# fet_driver.net
KiCad netlist of a schematic drawn in Altium Designer
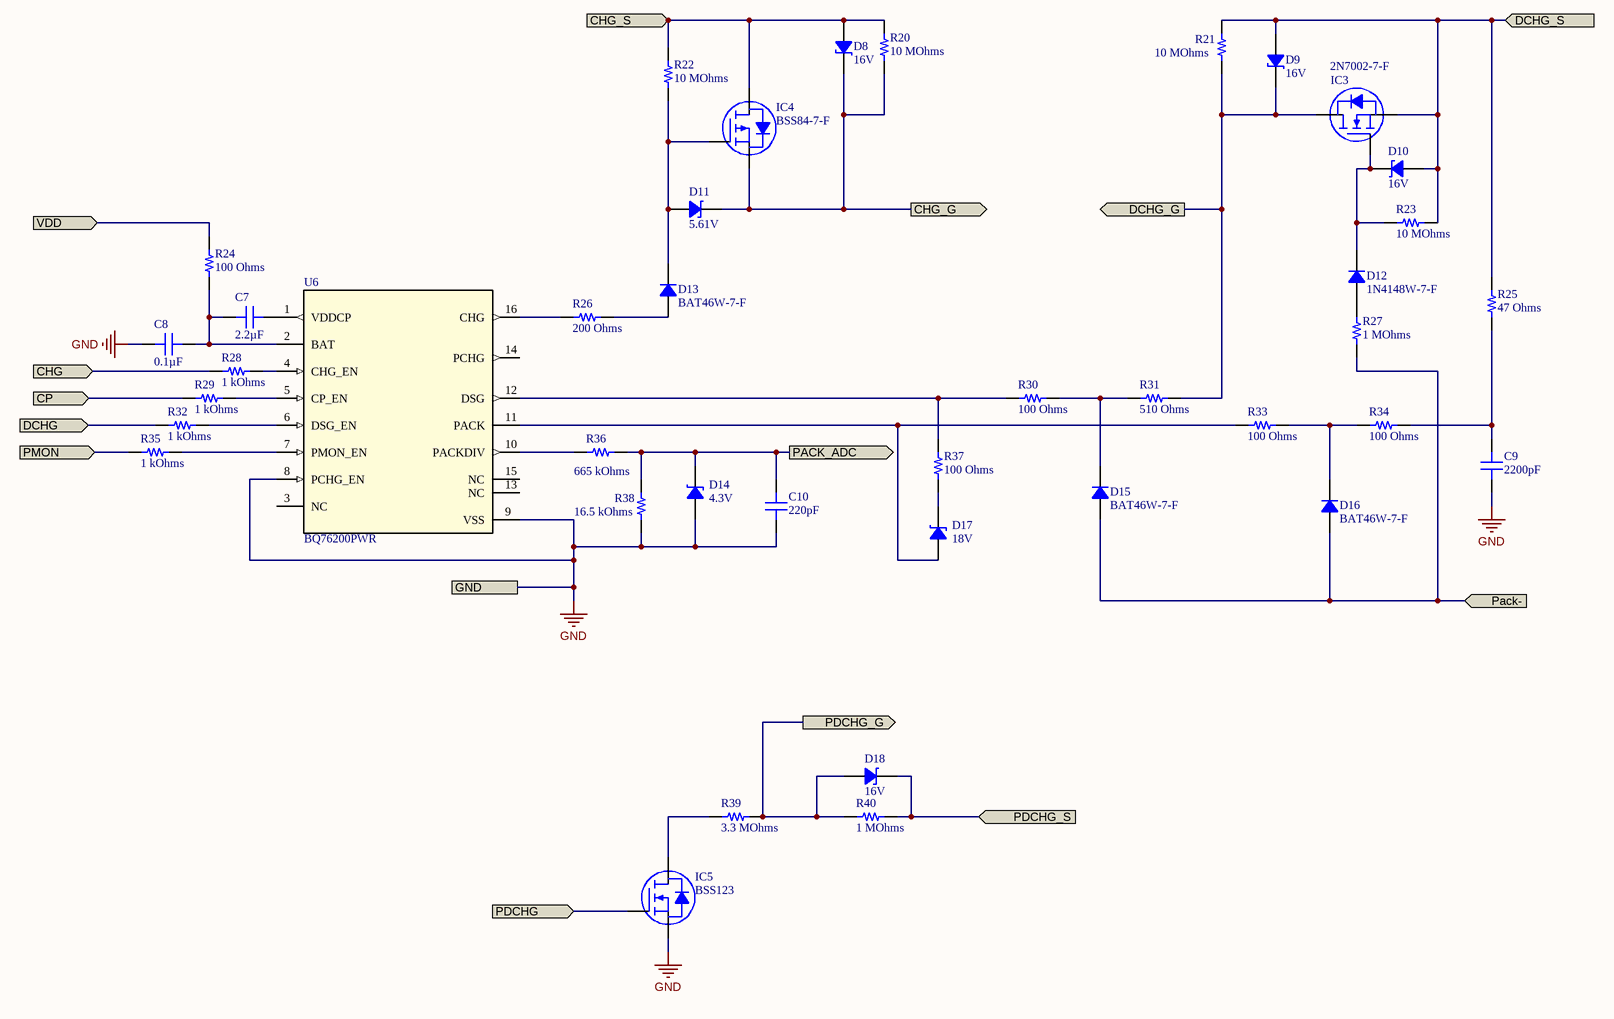
[diagram p0: fet_driver.SchDoc]

(export (version "E")
  (design (tool "Eeschema 10.0.6"))
  (components
    (comp (ref "C7")
      (value "2.2µF")
      (footprint "CAP 1210_3225 - 2.5MM")
      (description "CAP CER 2.2UF 100V X7R 1210")
      (fields
        (field (name "PART NUMBER") "C3225X7R2A225K230AE")
        (field (name "MANUFACTURER") "TDK Corporation")
      )
      (libsource (lib "Celestial Altium Library - altium_library") (part "Capacitor"))
    )
    (comp (ref "C8")
      (value "0.1µF")
      (footprint "CAP 0603_1608")
      (description "CAP CER 0.1UF 100V X7R 0603")
      (fields
        (field (name "PART NUMBER") "GCJ188R72A104KA01D")
        (field (name "MANUFACTURER") "Murata Electronics")
      )
      (libsource (lib "Celestial Altium Library - altium_library") (part "Capacitor"))
    )
    (comp (ref "C9")
      (value "2200pF")
      (footprint "CAP 0603_1608")
      (description "CAP CER 2200PF 100V X7R 0603")
      (fields
        (field (name "PART NUMBER") "CGA3E2X7R2A222K080AE")
        (field (name "MANUFACTURER") "TDK Corporation")
      )
      (libsource (lib "Celestial Altium Library - altium_library") (part "Capacitor"))
    )
    (comp (ref "C10")
      (value "220pF")
      (footprint "CAP 0603_1608")
      (description "CAP CER 220PF 50V X7R 0603")
      (fields (field (name "PART NUMBER") "CC0603KRX7R9BB221") (field (name "MANUFACTURER") "Yageo"))
      (libsource (lib "Celestial Altium Library - altium_library") (part "Capacitor"))
    )
    (comp (ref "D8")
      (value "MMSZ5246B-7-F")
      (footprint "SOD-123")
      (description "DIODE ZENER 16V 500MW SOD123")
      (fields
        (field (name "MANUFACTURER") "Diodes Incorporated")
        (field (name "TOLERANCE") "±5%")
        (field (name "VOLTAGE - ZENER (NOM) (VZ)") "16V")
      )
      (libsource (lib "Celestial Altium Library - altium_library") (part "Diode Zener"))
    )
    (comp (ref "D9")
      (value "MMSZ5246B-7-F")
      (footprint "SOD-123")
      (description "DIODE ZENER 16V 500MW SOD123")
      (fields
        (field (name "MANUFACTURER") "Diodes Incorporated")
        (field (name "TOLERANCE") "±5%")
        (field (name "VOLTAGE - ZENER (NOM) (VZ)") "16V")
      )
      (libsource (lib "Celestial Altium Library - altium_library") (part "Diode Zener"))
    )
    (comp (ref "D10")
      (value "MMSZ5246B-7-F")
      (footprint "SOD-123")
      (description "DIODE ZENER 16V 500MW SOD123")
      (fields
        (field (name "MANUFACTURER") "Diodes Incorporated")
        (field (name "TOLERANCE") "±5%")
        (field (name "VOLTAGE - ZENER (NOM) (VZ)") "16V")
      )
      (libsource (lib "Celestial Altium Library - altium_library") (part "Diode Zener"))
    )
    (comp (ref "D11")
      (value "MM5Z5V6ST1G")
      (footprint "SOD523F")
      (description "DIODE ZENER 5.61V 500MW SOD523")
      (fields
        (field (name "MANUFACTURER") "ON Semiconductor")
        (field (name "TOLERANCE") "±2%")
        (field (name "VOLTAGE - ZENER (NOM) (VZ)") "5.61V")
      )
      (libsource (lib "Celestial Altium Library - altium_library") (part "Diode Zener"))
    )
    (comp (ref "D12")
      (value "1N4148W-7-F")
      (footprint "SOD-123")
      (description "DIODE GEN PURP 100V 300MA SOD123")
      (fields (field (name "MANUFACTURER") "Diodes Incorporated"))
      (libsource (lib "Celestial Altium Library - altium_library") (part "Diode"))
    )
    (comp (ref "D13")
      (value "BAT46W-7-F")
      (footprint "SOD-123")
      (description "DIODE SCHOTTKY 100V 150MA SOD123")
      (fields (field (name "MANUFACTURER") "Diodes Incorporated"))
      (libsource (lib "Celestial Altium Library - altium_library") (part "Diode"))
    )
    (comp (ref "D14")
      (value "MMSZ5229BT1G")
      (footprint "SOD-123")
      (description "DIODE ZENER 4.3V 500MW SOD123")
      (fields
        (field (name "MANUFACTURER") "ON Semiconductor")
        (field (name "TOLERANCE") "±5%")
        (field (name "VOLTAGE - ZENER (NOM) (VZ)") "4.3V")
      )
      (libsource (lib "Celestial Altium Library - altium_library") (part "Diode Zener"))
    )
    (comp (ref "D15")
      (value "BAT46W-7-F")
      (footprint "SOD-123")
      (description "DIODE SCHOTTKY 100V 150MA SOD123")
      (fields (field (name "MANUFACTURER") "Diodes Incorporated"))
      (libsource (lib "Celestial Altium Library - altium_library") (part "Diode"))
    )
    (comp (ref "D16")
      (value "BAT46W-7-F")
      (footprint "SOD-123")
      (description "DIODE SCHOTTKY 100V 150MA SOD123")
      (fields (field (name "MANUFACTURER") "Diodes Incorporated"))
      (libsource (lib "Celestial Altium Library - altium_library") (part "Diode"))
    )
    (comp (ref "D17")
      (value "MMBZ5248BT-7-F")
      (footprint "DIODES SOT-523")
      (description "DIODE ZENER 18V 150MW SOT523")
      (fields
        (field (name "MANUFACTURER") "Diodes Incorporated")
        (field (name "TOLERANCE") "±5%")
        (field (name "VOLTAGE - ZENER (NOM) (VZ)") "18V")
      )
      (libsource (lib "Celestial Altium Library - altium_library") (part "Diode Zener"))
    )
    (comp (ref "D18")
      (value "MMSZ5246B-7-F")
      (footprint "SOD-123")
      (description "DIODE ZENER 16V 500MW SOD123")
      (fields
        (field (name "MANUFACTURER") "Diodes Incorporated")
        (field (name "TOLERANCE") "±5%")
        (field (name "VOLTAGE - ZENER (NOM) (VZ)") "16V")
      )
      (libsource (lib "Celestial Altium Library - altium_library") (part "Diode Zener"))
    )
    (comp (ref "IC3")
      (value "2N7002-7-F")
      (footprint "DIODES SOT-23-3")
      (description "MOSFET N-CH 60V 115MA SOT23-3")
      (fields (field (name "MANUFACTURER") "Diodes Incorporated"))
      (libsource (lib "Celestial Altium Library - altium_library") (part "DIODES INC MOSFET N-CH SOT-23-3"))
    )
    (comp (ref "IC4")
      (value "BSS84-7-F")
      (footprint "DIODES SOT-23-3")
      (description "MOSFET P-CH 50V 130MA SOT23-3")
      (fields (field (name "MANUFACTURER") "Diodes Incorporated"))
      (libsource (lib "Celestial Altium Library - altium_library") (part "DIODES MOSFET P-CH SOT-23-3"))
    )
    (comp (ref "IC5")
      (value "BSS123")
      (footprint "ON SEMI SOT-23-3")
      (description "MOSFET N-CH 100V 170MA SOT-23")
      (fields (field (name "MANUFACTURER") "ON Semiconductor"))
      (libsource (lib "Celestial Altium Library - altium_library") (part "ON SEMI MOSFET N-CH SOT-23-3"))
    )
    (comp (ref "R20")
      (value "10 MOhms")
      (footprint "RES 0603_1608")
      (description "RES SMD 10M OHM 1% 1/10W 0603")
      (fields (field (name "PART NUMBER") "CRCW060310M0FKEA") (field (name "MANUFACTURER") "Vishay Dale"))
      (libsource (lib "Celestial Altium Library - altium_library") (part "Resistor"))
    )
    (comp (ref "R21")
      (value "10 MOhms")
      (footprint "RES 0603_1608")
      (description "RES SMD 10M OHM 1% 1/10W 0603")
      (fields (field (name "PART NUMBER") "CRCW060310M0FKEA") (field (name "MANUFACTURER") "Vishay Dale"))
      (libsource (lib "Celestial Altium Library - altium_library") (part "Resistor"))
    )
    (comp (ref "R22")
      (value "10 MOhms")
      (footprint "RES 0603_1608")
      (description "RES SMD 10M OHM 1% 1/10W 0603")
      (fields (field (name "PART NUMBER") "CRCW060310M0FKEA") (field (name "MANUFACTURER") "Vishay Dale"))
      (libsource (lib "Celestial Altium Library - altium_library") (part "Resistor"))
    )
    (comp (ref "R23")
      (value "10 MOhms")
      (footprint "RES 0603_1608")
      (description "RES SMD 10M OHM 1% 1/10W 0603")
      (fields (field (name "PART NUMBER") "CRCW060310M0FKEA") (field (name "MANUFACTURER") "Vishay Dale"))
      (libsource (lib "Celestial Altium Library - altium_library") (part "Resistor"))
    )
    (comp (ref "R24")
      (value "100 Ohms")
      (footprint "RES 0603_1608")
      (description "RES SMD 100 OHM 1% 1/10W 0603")
      (fields (field (name "PART NUMBER") "CRCW0603100RFKTA") (field (name "MANUFACTURER") "Vishay Dale"))
      (libsource (lib "Celestial Altium Library - altium_library") (part "Resistor"))
    )
    (comp (ref "R25")
      (value "47 Ohms")
      (footprint "RES 0603_1608")
      (description "RES SMD 47 OHM 1% 1/10W 0603")
      (fields (field (name "PART NUMBER") "CRCW060347R0FKEA") (field (name "MANUFACTURER") "Vishay Dale"))
      (libsource (lib "Celestial Altium Library - altium_library") (part "Resistor"))
    )
    (comp (ref "R26")
      (value "200 Ohms")
      (footprint "RES 0603_1608")
      (description "RES SMD 200 OHM 1% 1/10W 0603")
      (fields (field (name "PART NUMBER") "CRCW0603200RFKEA") (field (name "MANUFACTURER") "Vishay Dale"))
      (libsource (lib "Celestial Altium Library - altium_library") (part "Resistor"))
    )
    (comp (ref "R27")
      (value "1 MOhms")
      (footprint "RES 0603_1608")
      (description "RES SMD 1M OHM 1% 1/10W 0603")
      (fields (field (name "PART NUMBER") "CRCW06031M00FKEA") (field (name "MANUFACTURER") "Vishay Dale"))
      (libsource (lib "Celestial Altium Library - altium_library") (part "Resistor"))
    )
    (comp (ref "R28")
      (value "1 kOhms")
      (footprint "RES 0603_1608")
      (description "RES SMD 1K OHM 1% 1/10W 0603")
      (fields (field (name "PART NUMBER") "CRCW06031K00FKEA") (field (name "MANUFACTURER") "Vishay Dale"))
      (libsource (lib "Celestial Altium Library - altium_library") (part "Resistor"))
    )
    (comp (ref "R29")
      (value "1 kOhms")
      (footprint "RES 0603_1608")
      (description "RES SMD 1K OHM 1% 1/10W 0603")
      (fields (field (name "PART NUMBER") "CRCW06031K00FKEA") (field (name "MANUFACTURER") "Vishay Dale"))
      (libsource (lib "Celestial Altium Library - altium_library") (part "Resistor"))
    )
    (comp (ref "R30")
      (value "100 Ohms")
      (footprint "RES 0603_1608")
      (description "RES SMD 100 OHM 1% 1/10W 0603")
      (fields (field (name "PART NUMBER") "CRCW0603100RFKTA") (field (name "MANUFACTURER") "Vishay Dale"))
      (libsource (lib "Celestial Altium Library - altium_library") (part "Resistor"))
    )
    (comp (ref "R31")
      (value "510 Ohms")
      (footprint "RES 0603_1608")
      (description "RES SMD 510 OHM 1% 1/10W 0603")
      (fields (field (name "PART NUMBER") "CRCW0603510RFKEA") (field (name "MANUFACTURER") "Vishay Dale"))
      (libsource (lib "Celestial Altium Library - altium_library") (part "Resistor"))
    )
    (comp (ref "R32")
      (value "1 kOhms")
      (footprint "RES 0603_1608")
      (description "RES SMD 1K OHM 1% 1/10W 0603")
      (fields (field (name "PART NUMBER") "CRCW06031K00FKEA") (field (name "MANUFACTURER") "Vishay Dale"))
      (libsource (lib "Celestial Altium Library - altium_library") (part "Resistor"))
    )
    (comp (ref "R33")
      (value "100 Ohms")
      (footprint "RES 0603_1608")
      (description "RES SMD 100 OHM 1% 1/10W 0603")
      (fields (field (name "PART NUMBER") "CRCW0603100RFKTA") (field (name "MANUFACTURER") "Vishay Dale"))
      (libsource (lib "Celestial Altium Library - altium_library") (part "Resistor"))
    )
    (comp (ref "R34")
      (value "100 Ohms")
      (footprint "RES 0603_1608")
      (description "RES SMD 100 OHM 1% 1/10W 0603")
      (fields (field (name "PART NUMBER") "CRCW0603100RFKTA") (field (name "MANUFACTURER") "Vishay Dale"))
      (libsource (lib "Celestial Altium Library - altium_library") (part "Resistor"))
    )
    (comp (ref "R35")
      (value "1 kOhms")
      (footprint "RES 0603_1608")
      (description "RES SMD 1K OHM 1% 1/10W 0603")
      (fields (field (name "PART NUMBER") "CRCW06031K00FKEA") (field (name "MANUFACTURER") "Vishay Dale"))
      (libsource (lib "Celestial Altium Library - altium_library") (part "Resistor"))
    )
    (comp (ref "R36")
      (value "665 kOhms")
      (footprint "RES 0603_1608")
      (description "RES SMD 665K OHM 1% 1/10W 0603")
      (fields (field (name "PART NUMBER") "RC0603FR-07665KL") (field (name "MANUFACTURER") "Yageo"))
      (libsource (lib "Celestial Altium Library - altium_library") (part "Resistor"))
    )
    (comp (ref "R37")
      (value "100 Ohms")
      (footprint "RES 0603_1608")
      (description "RES SMD 100 OHM 1% 1/10W 0603")
      (fields (field (name "PART NUMBER") "CRCW0603100RFKTA") (field (name "MANUFACTURER") "Vishay Dale"))
      (libsource (lib "Celestial Altium Library - altium_library") (part "Resistor"))
    )
    (comp (ref "R38")
      (value "16.5 kOhms")
      (footprint "RES 0603_1608")
      (description "RES SMD 16.5K OHM 1% 1/10W 0603")
      (fields (field (name "PART NUMBER") "CRCW060316K5FKEA") (field (name "MANUFACTURER") "Vishay Dale"))
      (libsource (lib "Celestial Altium Library - altium_library") (part "Resistor"))
    )
    (comp (ref "R39")
      (value "3.3 MOhms")
      (footprint "RES 0603_1608")
      (description "RES SMD 3.3M OHM 1% 1/10W 0603")
      (fields (field (name "PART NUMBER") "CRCW06033M30FKEA") (field (name "MANUFACTURER") "Vishay Dale"))
      (libsource (lib "Celestial Altium Library - altium_library") (part "Resistor"))
    )
    (comp (ref "R40")
      (value "1 MOhms")
      (footprint "RES 0603_1608")
      (description "RES SMD 1M OHM 1% 1/10W 0603")
      (fields (field (name "PART NUMBER") "CRCW06031M00FKEA") (field (name "MANUFACTURER") "Vishay Dale"))
      (libsource (lib "Celestial Altium Library - altium_library") (part "Resistor"))
    )
    (comp (ref "U6")
      (value "BQ76200PWR")
      (footprint "TSSOP_16")
      (description "Battery Battery Protection IC Multi-Chemistry 16-TSSOP")
      (fields
        (field (name "ALTERNATE_PARTNUMBER") "BQ76200PW")
        (field (name "MANUFACTURER") "Texas Instruments")
        (field (name "COPYRIGHT") "Copyright (C) 2018 Accelerated Designs. All rights reserved")
      )
      (libsource (lib "bms") (part "BQ76200PWR"))
    )
  )
  (nets
    (net (code "1") (name "/CHG") (class "Default")
      (node (ref "R28") (pin "1") (pinfunction "1_1") (pintype "passive"))
    )
    (net (code "2") (name "/CHG_G") (class "Default")
      (node (ref "D11") (pin "2") (pinfunction "2_2") (pintype "passive"))
      (node (ref "D8") (pin "2") (pinfunction "2_2") (pintype "passive"))
      (node (ref "IC4") (pin "2") (pinfunction "S_2") (pintype "passive"))
      (node (ref "R20") (pin "1") (pinfunction "1_1") (pintype "passive"))
    )
    (net (code "3") (name "/CHG_S") (class "Default")
      (node (ref "D8") (pin "1") (pinfunction "1_1") (pintype "passive"))
      (node (ref "IC4") (pin "3") (pinfunction "D_3") (pintype "passive"))
      (node (ref "R20") (pin "2") (pinfunction "2_2") (pintype "passive"))
      (node (ref "R22") (pin "2") (pinfunction "2_2") (pintype "passive"))
    )
    (net (code "4") (name "/CP") (class "Default")
      (node (ref "R29") (pin "1") (pinfunction "1_1") (pintype "passive"))
    )
    (net (code "5") (name "/DCHG") (class "Default")
      (node (ref "R32") (pin "1") (pinfunction "1_1") (pintype "passive"))
    )
    (net (code "6") (name "/DCHG_G") (class "Default")
      (node (ref "D9") (pin "2") (pinfunction "2_2") (pintype "passive"))
      (node (ref "IC3") (pin "3") (pinfunction "D_3") (pintype "passive"))
      (node (ref "R21") (pin "1") (pinfunction "1_1") (pintype "passive"))
      (node (ref "R31") (pin "2") (pinfunction "2_2") (pintype "passive"))
    )
    (net (code "7") (name "/DCHG_S") (class "Default")
      (node (ref "D10") (pin "1") (pinfunction "1_1") (pintype "passive"))
      (node (ref "D9") (pin "1") (pinfunction "1_1") (pintype "passive"))
      (node (ref "IC3") (pin "2") (pinfunction "S_2") (pintype "passive"))
      (node (ref "R21") (pin "2") (pinfunction "2_2") (pintype "passive"))
      (node (ref "R23") (pin "1") (pinfunction "1_1") (pintype "passive"))
      (node (ref "R25") (pin "2") (pinfunction "2_2") (pintype "passive"))
    )
    (net (code "8") (name "/PACK_ADC") (class "Default")
      (node (ref "C10") (pin "2") (pinfunction "2_2") (pintype "passive"))
      (node (ref "D14") (pin "2") (pinfunction "2_2") (pintype "passive"))
      (node (ref "R36") (pin "2") (pinfunction "2_2") (pintype "passive"))
      (node (ref "R38") (pin "2") (pinfunction "2_2") (pintype "passive"))
    )
    (net (code "9") (name "/PDCHG") (class "Default")
      (node (ref "IC5") (pin "1") (pinfunction "G_1") (pintype "passive"))
    )
    (net (code "10") (name "/PDCHG_G") (class "Default")
      (node (ref "D18") (pin "1") (pinfunction "1_1") (pintype "passive"))
      (node (ref "R39") (pin "2") (pinfunction "2_2") (pintype "passive"))
      (node (ref "R40") (pin "2") (pinfunction "2_2") (pintype "passive"))
    )
    (net (code "11") (name "/PDCHG_S") (class "Default")
      (node (ref "D18") (pin "2") (pinfunction "2_2") (pintype "passive"))
      (node (ref "R40") (pin "1") (pinfunction "1_1") (pintype "passive"))
    )
    (net (code "12") (name "/PMON") (class "Default")
      (node (ref "R35") (pin "1") (pinfunction "1_1") (pintype "passive"))
    )
    (net (code "13") (name "/Pack-") (class "Default")
      (node (ref "D15") (pin "1") (pinfunction "1_1") (pintype "passive"))
      (node (ref "D16") (pin "1") (pinfunction "1_1") (pintype "passive"))
      (node (ref "R27") (pin "1") (pinfunction "1_1") (pintype "passive"))
    )
    (net (code "14") (name "/VDD") (class "Default")
      (node (ref "R24") (pin "2") (pinfunction "2_2") (pintype "passive"))
    )
    (net (code "15") (name "GND") (class "Default")
      (node (ref "C10") (pin "1") (pinfunction "1_1") (pintype "passive"))
      (node (ref "C8") (pin "1") (pinfunction "1_1") (pintype "passive"))
      (node (ref "C9") (pin "1") (pinfunction "1_1") (pintype "passive"))
      (node (ref "D14") (pin "1") (pinfunction "1_1") (pintype "passive"))
      (node (ref "IC5") (pin "2") (pinfunction "S_2") (pintype "passive"))
      (node (ref "R38") (pin "1") (pinfunction "1_1") (pintype "passive"))
      (node (ref "U6") (pin "8") (pinfunction "PCHG_EN_8") (pintype "input"))
      (node (ref "U6") (pin "9") (pinfunction "VSS_9") (pintype "power_in"))
    )
    (net (code "16") (name "Net-(C9-Pad2)") (class "Default")
      (node (ref "C9") (pin "2") (pinfunction "2_2") (pintype "passive"))
      (node (ref "R25") (pin "1") (pinfunction "1_1") (pintype "passive"))
      (node (ref "R34") (pin "1") (pinfunction "1_1") (pintype "passive"))
    )
    (net (code "17") (name "Net-(D12-Pad1)") (class "Default")
      (node (ref "D12") (pin "1") (pinfunction "1_1") (pintype "passive"))
      (node (ref "R27") (pin "2") (pinfunction "2_2") (pintype "passive"))
    )
    (net (code "18") (name "Net-(D13-Pad1)") (class "Default")
      (node (ref "D13") (pin "1") (pinfunction "1_1") (pintype "passive"))
      (node (ref "R26") (pin "2") (pinfunction "2_2") (pintype "passive"))
    )
    (net (code "19") (name "Net-(D15-Pad2)") (class "Default")
      (node (ref "D15") (pin "2") (pinfunction "2_2") (pintype "passive"))
      (node (ref "R30") (pin "1") (pinfunction "1_1") (pintype "passive"))
      (node (ref "R31") (pin "1") (pinfunction "1_1") (pintype "passive"))
    )
    (net (code "20") (name "Net-(D16-Pad2)") (class "Default")
      (node (ref "D16") (pin "2") (pinfunction "2_2") (pintype "passive"))
      (node (ref "R33") (pin "1") (pinfunction "1_1") (pintype "passive"))
      (node (ref "R34") (pin "2") (pinfunction "2_2") (pintype "passive"))
    )
    (net (code "21") (name "Net-(D17-Pad2)") (class "Default")
      (node (ref "D17") (pin "2") (pinfunction "2_2") (pintype "passive"))
      (node (ref "R37") (pin "2") (pinfunction "2_2") (pintype "passive"))
    )
    (net (code "22") (name "Net-(IC3-G)") (class "Default")
      (node (ref "D10") (pin "2") (pinfunction "2_2") (pintype "passive"))
      (node (ref "D12") (pin "2") (pinfunction "2_2") (pintype "passive"))
      (node (ref "IC3") (pin "1") (pinfunction "G_1") (pintype "passive"))
      (node (ref "R23") (pin "2") (pinfunction "2_2") (pintype "passive"))
    )
    (net (code "23") (name "Net-(IC4-G)") (class "Default")
      (node (ref "D11") (pin "1") (pinfunction "1_1") (pintype "passive"))
      (node (ref "D13") (pin "2") (pinfunction "2_2") (pintype "passive"))
      (node (ref "IC4") (pin "1") (pinfunction "G_1") (pintype "passive"))
      (node (ref "R22") (pin "1") (pinfunction "1_1") (pintype "passive"))
    )
    (net (code "24") (name "Net-(IC5-D)") (class "Default")
      (node (ref "IC5") (pin "3") (pinfunction "D_3") (pintype "passive"))
      (node (ref "R39") (pin "1") (pinfunction "1_1") (pintype "passive"))
    )
    (net (code "25") (name "Net-(U6-BAT)") (class "Default")
      (node (ref "C7") (pin "1") (pinfunction "1_1") (pintype "passive"))
      (node (ref "C8") (pin "2") (pinfunction "2_2") (pintype "passive"))
      (node (ref "R24") (pin "1") (pinfunction "1_1") (pintype "passive"))
      (node (ref "U6") (pin "2") (pinfunction "BAT_2") (pintype "power_in"))
    )
    (net (code "26") (name "Net-(U6-CHG)") (class "Default")
      (node (ref "R26") (pin "1") (pinfunction "1_1") (pintype "passive"))
      (node (ref "U6") (pin "16") (pinfunction "CHG_16") (pintype "output"))
    )
    (net (code "27") (name "Net-(U6-CHG_EN)") (class "Default")
      (node (ref "R28") (pin "2") (pinfunction "2_2") (pintype "passive"))
      (node (ref "U6") (pin "4") (pinfunction "CHG_EN_4") (pintype "input"))
    )
    (net (code "28") (name "Net-(U6-CP_EN)") (class "Default")
      (node (ref "R29") (pin "2") (pinfunction "2_2") (pintype "passive"))
      (node (ref "U6") (pin "5") (pinfunction "CP_EN_5") (pintype "input"))
    )
    (net (code "29") (name "Net-(U6-DSG)") (class "Default")
      (node (ref "R30") (pin "2") (pinfunction "2_2") (pintype "passive"))
      (node (ref "R37") (pin "1") (pinfunction "1_1") (pintype "passive"))
      (node (ref "U6") (pin "12") (pinfunction "DSG_12") (pintype "output"))
    )
    (net (code "30") (name "Net-(U6-DSG_EN)") (class "Default")
      (node (ref "R32") (pin "2") (pinfunction "2_2") (pintype "passive"))
      (node (ref "U6") (pin "6") (pinfunction "DSG_EN_6") (pintype "input"))
    )
    (net (code "31") (name "Net-(U6-PACK)") (class "Default")
      (node (ref "D17") (pin "1") (pinfunction "1_1") (pintype "passive"))
      (node (ref "R33") (pin "2") (pinfunction "2_2") (pintype "passive"))
      (node (ref "U6") (pin "11") (pinfunction "PACK_11") (pintype "power_in"))
    )
    (net (code "32") (name "Net-(U6-PACKDIV)") (class "Default")
      (node (ref "R36") (pin "1") (pinfunction "1_1") (pintype "passive"))
      (node (ref "U6") (pin "10") (pinfunction "PACKDIV_10") (pintype "output"))
    )
    (net (code "33") (name "Net-(U6-PMON_EN)") (class "Default")
      (node (ref "R35") (pin "2") (pinfunction "2_2") (pintype "passive"))
      (node (ref "U6") (pin "7") (pinfunction "PMON_EN_7") (pintype "input"))
    )
    (net (code "34") (name "Net-(U6-VDDCP)") (class "Default")
      (node (ref "C7") (pin "2") (pinfunction "2_2") (pintype "passive"))
      (node (ref "U6") (pin "1") (pinfunction "VDDCP_1") (pintype "output"))
    )
    (net (code "35") (name "unconnected-(U6-NC-Pad3)") (class "Default")
      (node (ref "U6") (pin "3") (pinfunction "NC_3") (pintype "passive"))
    )
    (net (code "36") (name "unconnected-(U6-NC-Pad13)") (class "Default")
      (node (ref "U6") (pin "13") (pinfunction "NC_13") (pintype "passive"))
    )
    (net (code "37") (name "unconnected-(U6-NC-Pad15)") (class "Default")
      (node (ref "U6") (pin "15") (pinfunction "NC_15") (pintype "passive"))
    )
    (net (code "38") (name "unconnected-(U6-PCHG-Pad14)") (class "Default")
      (node (ref "U6") (pin "14") (pinfunction "PCHG_14") (pintype "output"))
    )
  )
)
